# Output_v2_0.net
KiCad netlist of a schematic drawn in EAGLE
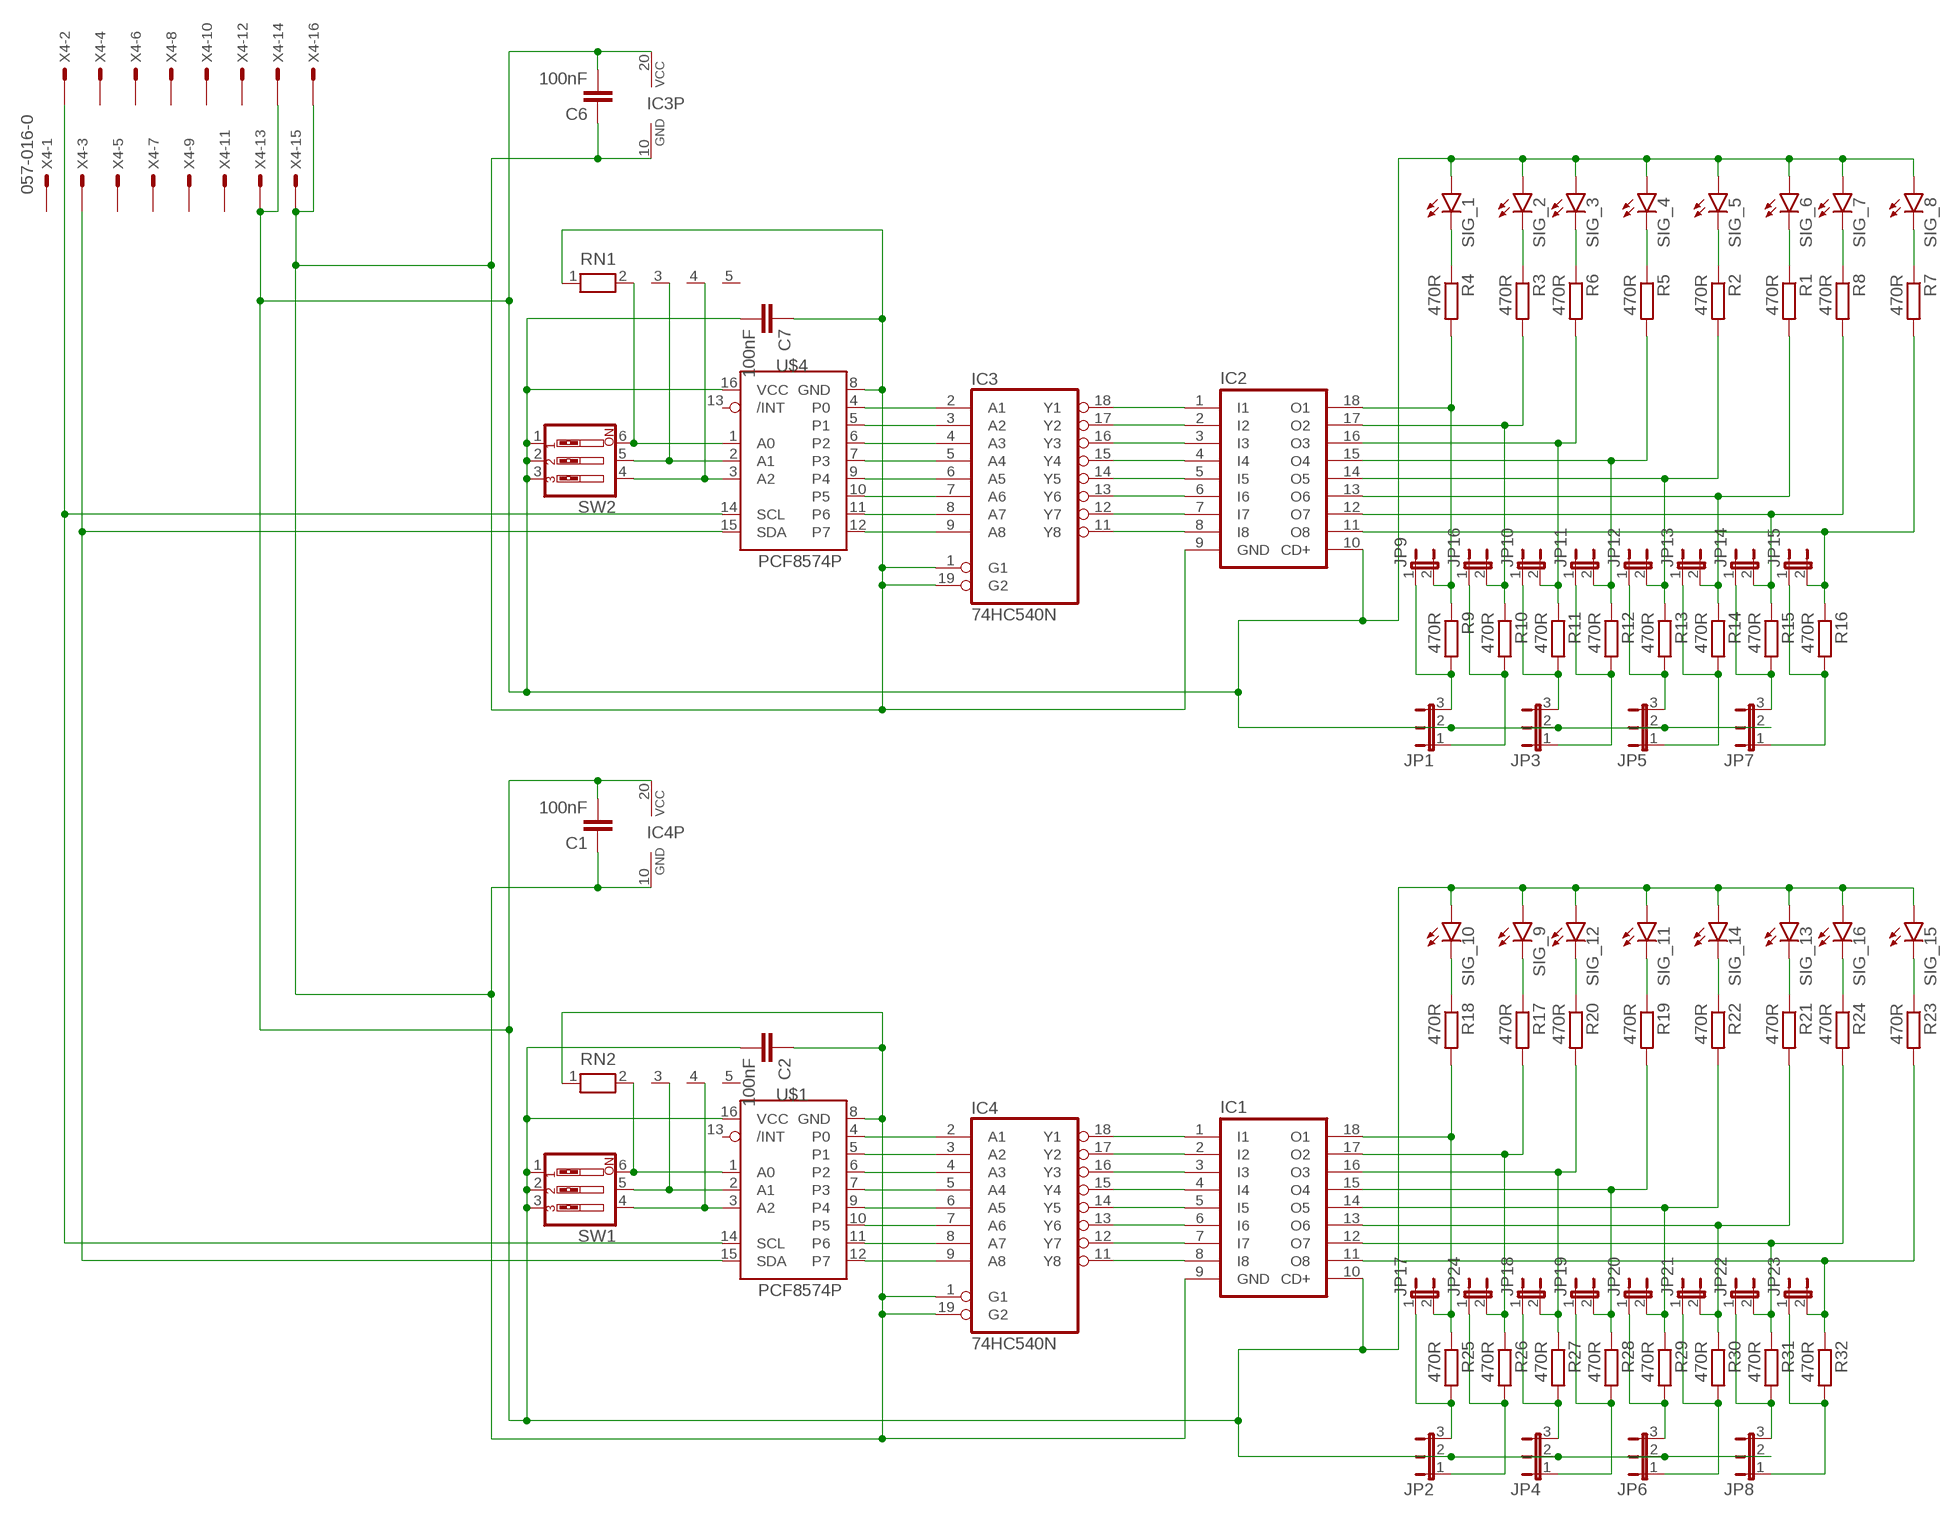
[diagram p0: schematic, sheet 1]

(export (version "E")
  (design (tool "Eeschema 10.0.6"))
  (components
    (comp (ref "C1")
      (value "100nF")
      (footprint "eagle-import:C025-024X044")
      (libsource (lib "eagle-import") (part "C-EU025-024X044"))
    )
    (comp (ref "C2")
      (value "100nF")
      (footprint "eagle-import:C025-024X044")
      (libsource (lib "eagle-import") (part "C-EU025-024X044"))
    )
    (comp (ref "C6")
      (value "100nF")
      (footprint "eagle-import:C025-024X044")
      (libsource (lib "eagle-import") (part "C-EU025-024X044"))
    )
    (comp (ref "C7")
      (value "100nF")
      (footprint "eagle-import:C025-024X044")
      (libsource (lib "eagle-import") (part "C-EU025-024X044"))
    )
    (comp (ref "IC1")
      (value "ULN2803A")
      (footprint "eagle-import:DIL18")
      (libsource (lib "eagle-import") (part "ULN2803A"))
    )
    (comp (ref "IC2")
      (value "ULN2803A")
      (footprint "eagle-import:DIL18")
      (libsource (lib "eagle-import") (part "ULN2803A"))
    )
    (comp (ref "IC3")
      (value "74HC540N")
      (footprint "eagle-import:DIL20")
      (libsource (lib "eagle-import") (part "74540NHC"))
    )
    (comp (ref "IC4")
      (value "74HC540N")
      (footprint "eagle-import:DIL20")
      (libsource (lib "eagle-import") (part "74540NHC"))
    )
    (comp (ref "JP1")
      (value "JP2E")
      (footprint "eagle-import:JP2")
      (libsource (lib "eagle-import") (part "JP2E"))
    )
    (comp (ref "JP2")
      (value "JP2E")
      (footprint "eagle-import:JP2")
      (libsource (lib "eagle-import") (part "JP2E"))
    )
    (comp (ref "JP3")
      (value "JP2E")
      (footprint "eagle-import:JP2")
      (libsource (lib "eagle-import") (part "JP2E"))
    )
    (comp (ref "JP4")
      (value "JP2E")
      (footprint "eagle-import:JP2")
      (libsource (lib "eagle-import") (part "JP2E"))
    )
    (comp (ref "JP5")
      (value "JP2E")
      (footprint "eagle-import:JP2")
      (libsource (lib "eagle-import") (part "JP2E"))
    )
    (comp (ref "JP6")
      (value "JP2E")
      (footprint "eagle-import:JP2")
      (libsource (lib "eagle-import") (part "JP2E"))
    )
    (comp (ref "JP7")
      (value "JP2E")
      (footprint "eagle-import:JP2")
      (libsource (lib "eagle-import") (part "JP2E"))
    )
    (comp (ref "JP8")
      (value "JP2E")
      (footprint "eagle-import:JP2")
      (libsource (lib "eagle-import") (part "JP2E"))
    )
    (comp (ref "JP9")
      (value "JP1E")
      (footprint "eagle-import:JP1")
      (libsource (lib "eagle-import") (part "JP1E"))
    )
    (comp (ref "JP10")
      (value "JP1E")
      (footprint "eagle-import:JP1")
      (libsource (lib "eagle-import") (part "JP1E"))
    )
    (comp (ref "JP11")
      (value "JP1E")
      (footprint "eagle-import:JP1")
      (libsource (lib "eagle-import") (part "JP1E"))
    )
    (comp (ref "JP12")
      (value "JP1E")
      (footprint "eagle-import:JP1")
      (libsource (lib "eagle-import") (part "JP1E"))
    )
    (comp (ref "JP13")
      (value "JP1E")
      (footprint "eagle-import:JP1")
      (libsource (lib "eagle-import") (part "JP1E"))
    )
    (comp (ref "JP14")
      (value "JP1E")
      (footprint "eagle-import:JP1")
      (libsource (lib "eagle-import") (part "JP1E"))
    )
    (comp (ref "JP15")
      (value "JP1E")
      (footprint "eagle-import:JP1")
      (libsource (lib "eagle-import") (part "JP1E"))
    )
    (comp (ref "JP16")
      (value "JP1E")
      (footprint "eagle-import:JP1")
      (libsource (lib "eagle-import") (part "JP1E"))
    )
    (comp (ref "JP17")
      (value "JP1E")
      (footprint "eagle-import:JP1")
      (libsource (lib "eagle-import") (part "JP1E"))
    )
    (comp (ref "JP18")
      (value "JP1E")
      (footprint "eagle-import:JP1")
      (libsource (lib "eagle-import") (part "JP1E"))
    )
    (comp (ref "JP19")
      (value "JP1E")
      (footprint "eagle-import:JP1")
      (libsource (lib "eagle-import") (part "JP1E"))
    )
    (comp (ref "JP20")
      (value "JP1E")
      (footprint "eagle-import:JP1")
      (libsource (lib "eagle-import") (part "JP1E"))
    )
    (comp (ref "JP21")
      (value "JP1E")
      (footprint "eagle-import:JP1")
      (libsource (lib "eagle-import") (part "JP1E"))
    )
    (comp (ref "JP22")
      (value "JP1E")
      (footprint "eagle-import:JP1")
      (libsource (lib "eagle-import") (part "JP1E"))
    )
    (comp (ref "JP23")
      (value "JP1E")
      (footprint "eagle-import:JP1")
      (libsource (lib "eagle-import") (part "JP1E"))
    )
    (comp (ref "JP24")
      (value "JP1E")
      (footprint "eagle-import:JP1")
      (libsource (lib "eagle-import") (part "JP1E"))
    )
    (comp (ref "R1")
      (value "470R")
      (footprint "eagle-import:0309_10")
      (libsource (lib "eagle-import") (part "R-EU_0309/10"))
    )
    (comp (ref "R2")
      (value "470R")
      (footprint "eagle-import:0309_10")
      (libsource (lib "eagle-import") (part "R-EU_0309/10"))
    )
    (comp (ref "R3")
      (value "470R")
      (footprint "eagle-import:0309_10")
      (libsource (lib "eagle-import") (part "R-EU_0309/10"))
    )
    (comp (ref "R4")
      (value "470R")
      (footprint "eagle-import:0309_10")
      (libsource (lib "eagle-import") (part "R-EU_0309/10"))
    )
    (comp (ref "R5")
      (value "470R")
      (footprint "eagle-import:0309_10")
      (libsource (lib "eagle-import") (part "R-EU_0309/10"))
    )
    (comp (ref "R6")
      (value "470R")
      (footprint "eagle-import:0309_10")
      (libsource (lib "eagle-import") (part "R-EU_0309/10"))
    )
    (comp (ref "R7")
      (value "470R")
      (footprint "eagle-import:0309_10")
      (libsource (lib "eagle-import") (part "R-EU_0309/10"))
    )
    (comp (ref "R8")
      (value "470R")
      (footprint "eagle-import:0309_10")
      (libsource (lib "eagle-import") (part "R-EU_0309/10"))
    )
    (comp (ref "R9")
      (value "470R")
      (footprint "eagle-import:0309_10")
      (libsource (lib "eagle-import") (part "R-EU_0309/10"))
    )
    (comp (ref "R10")
      (value "470R")
      (footprint "eagle-import:0309_10")
      (libsource (lib "eagle-import") (part "R-EU_0309/10"))
    )
    (comp (ref "R11")
      (value "470R")
      (footprint "eagle-import:0309_10")
      (libsource (lib "eagle-import") (part "R-EU_0309/10"))
    )
    (comp (ref "R12")
      (value "470R")
      (footprint "eagle-import:0309_10")
      (libsource (lib "eagle-import") (part "R-EU_0309/10"))
    )
    (comp (ref "R13")
      (value "470R")
      (footprint "eagle-import:0309_10")
      (libsource (lib "eagle-import") (part "R-EU_0309/10"))
    )
    (comp (ref "R14")
      (value "470R")
      (footprint "eagle-import:0309_10")
      (libsource (lib "eagle-import") (part "R-EU_0309/10"))
    )
    (comp (ref "R15")
      (value "470R")
      (footprint "eagle-import:0309_10")
      (libsource (lib "eagle-import") (part "R-EU_0309/10"))
    )
    (comp (ref "R16")
      (value "470R")
      (footprint "eagle-import:0309_10")
      (libsource (lib "eagle-import") (part "R-EU_0309/10"))
    )
    (comp (ref "R17")
      (value "470R")
      (footprint "eagle-import:0309_10")
      (libsource (lib "eagle-import") (part "R-EU_0309/10"))
    )
    (comp (ref "R18")
      (value "470R")
      (footprint "eagle-import:0309_10")
      (libsource (lib "eagle-import") (part "R-EU_0309/10"))
    )
    (comp (ref "R19")
      (value "470R")
      (footprint "eagle-import:0309_10")
      (libsource (lib "eagle-import") (part "R-EU_0309/10"))
    )
    (comp (ref "R20")
      (value "470R")
      (footprint "eagle-import:0309_10")
      (libsource (lib "eagle-import") (part "R-EU_0309/10"))
    )
    (comp (ref "R21")
      (value "470R")
      (footprint "eagle-import:0309_10")
      (libsource (lib "eagle-import") (part "R-EU_0309/10"))
    )
    (comp (ref "R22")
      (value "470R")
      (footprint "eagle-import:0309_10")
      (libsource (lib "eagle-import") (part "R-EU_0309/10"))
    )
    (comp (ref "R23")
      (value "470R")
      (footprint "eagle-import:0309_10")
      (libsource (lib "eagle-import") (part "R-EU_0309/10"))
    )
    (comp (ref "R24")
      (value "470R")
      (footprint "eagle-import:0309_10")
      (libsource (lib "eagle-import") (part "R-EU_0309/10"))
    )
    (comp (ref "R25")
      (value "470R")
      (footprint "eagle-import:0309_10")
      (libsource (lib "eagle-import") (part "R-EU_0309/10"))
    )
    (comp (ref "R26")
      (value "470R")
      (footprint "eagle-import:0309_10")
      (libsource (lib "eagle-import") (part "R-EU_0309/10"))
    )
    (comp (ref "R27")
      (value "470R")
      (footprint "eagle-import:0309_10")
      (libsource (lib "eagle-import") (part "R-EU_0309/10"))
    )
    (comp (ref "R28")
      (value "470R")
      (footprint "eagle-import:0309_10")
      (libsource (lib "eagle-import") (part "R-EU_0309/10"))
    )
    (comp (ref "R29")
      (value "470R")
      (footprint "eagle-import:0309_10")
      (libsource (lib "eagle-import") (part "R-EU_0309/10"))
    )
    (comp (ref "R30")
      (value "470R")
      (footprint "eagle-import:0309_10")
      (libsource (lib "eagle-import") (part "R-EU_0309/10"))
    )
    (comp (ref "R31")
      (value "470R")
      (footprint "eagle-import:0309_10")
      (libsource (lib "eagle-import") (part "R-EU_0309/10"))
    )
    (comp (ref "R32")
      (value "470R")
      (footprint "eagle-import:0309_10")
      (libsource (lib "eagle-import") (part "R-EU_0309/10"))
    )
    (comp (ref "RN1")
      (value "RN04")
      (footprint "eagle-import:RN-5")
      (libsource (lib "eagle-import") (part "RN04"))
    )
    (comp (ref "RN2")
      (value "RN04")
      (footprint "eagle-import:RN-5")
      (libsource (lib "eagle-import") (part "RN04"))
    )
    (comp (ref "SIG_1")
      (value "LED3MM")
      (footprint "eagle-import:LED3MM")
      (libsource (lib "eagle-import") (part "LED3MM"))
    )
    (comp (ref "SIG_2")
      (value "LED3MM")
      (footprint "eagle-import:LED3MM")
      (libsource (lib "eagle-import") (part "LED3MM"))
    )
    (comp (ref "SIG_3")
      (value "LED3MM")
      (footprint "eagle-import:LED3MM")
      (libsource (lib "eagle-import") (part "LED3MM"))
    )
    (comp (ref "SIG_4")
      (value "LED3MM")
      (footprint "eagle-import:LED3MM")
      (libsource (lib "eagle-import") (part "LED3MM"))
    )
    (comp (ref "SIG_5")
      (value "LED3MM")
      (footprint "eagle-import:LED3MM")
      (libsource (lib "eagle-import") (part "LED3MM"))
    )
    (comp (ref "SIG_6")
      (value "LED3MM")
      (footprint "eagle-import:LED3MM")
      (libsource (lib "eagle-import") (part "LED3MM"))
    )
    (comp (ref "SIG_7")
      (value "LED3MM")
      (footprint "eagle-import:LED3MM")
      (libsource (lib "eagle-import") (part "LED3MM"))
    )
    (comp (ref "SIG_8")
      (value "LED3MM")
      (footprint "eagle-import:LED3MM")
      (libsource (lib "eagle-import") (part "LED3MM"))
    )
    (comp (ref "SIG_9")
      (value "LED3MM")
      (footprint "eagle-import:LED3MM")
      (libsource (lib "eagle-import") (part "LED3MM"))
    )
    (comp (ref "SIG_10")
      (value "LED3MM")
      (footprint "eagle-import:LED3MM")
      (libsource (lib "eagle-import") (part "LED3MM"))
    )
    (comp (ref "SIG_11")
      (value "LED3MM")
      (footprint "eagle-import:LED3MM")
      (libsource (lib "eagle-import") (part "LED3MM"))
    )
    (comp (ref "SIG_12")
      (value "LED3MM")
      (footprint "eagle-import:LED3MM")
      (libsource (lib "eagle-import") (part "LED3MM"))
    )
    (comp (ref "SIG_13")
      (value "LED3MM")
      (footprint "eagle-import:LED3MM")
      (libsource (lib "eagle-import") (part "LED3MM"))
    )
    (comp (ref "SIG_14")
      (value "LED3MM")
      (footprint "eagle-import:LED3MM")
      (libsource (lib "eagle-import") (part "LED3MM"))
    )
    (comp (ref "SIG_15")
      (value "LED3MM")
      (footprint "eagle-import:LED3MM")
      (libsource (lib "eagle-import") (part "LED3MM"))
    )
    (comp (ref "SIG_16")
      (value "LED3MM")
      (footprint "eagle-import:LED3MM")
      (libsource (lib "eagle-import") (part "LED3MM"))
    )
    (comp (ref "SW1")
      (value "SW_DIP-3")
      (footprint "eagle-import:EDG-03")
      (libsource (lib "eagle-import") (part "SW_DIP-3"))
    )
    (comp (ref "SW2")
      (value "SW_DIP-3")
      (footprint "eagle-import:EDG-03")
      (libsource (lib "eagle-import") (part "SW_DIP-3"))
    )
    (comp (ref "U$1")
      (value "PCF8574P")
      (footprint "eagle-import:DIL16")
      (libsource (lib "eagle-import") (part "PCF8574P"))
    )
    (comp (ref "U$4")
      (value "PCF8574P")
      (footprint "eagle-import:DIL16")
      (libsource (lib "eagle-import") (part "PCF8574P"))
    )
    (comp (ref "X4")
      (value "057-016-0")
      (footprint "eagle-import:057-016-0")
      (libsource (lib "eagle-import") (part "057-016-0"))
    )
  )
  (nets
    (net (code "1") (name "Net-(IC1-CD+)") (class "Default")
      (node (ref "C1") (pin "2") (pinfunction "2_2") (pintype "passive"))
      (node (ref "C2") (pin "2") (pinfunction "2_2") (pintype "passive"))
      (node (ref "C6") (pin "2") (pinfunction "2_2") (pintype "passive"))
      (node (ref "C7") (pin "2") (pinfunction "2_2") (pintype "passive"))
      (node (ref "IC1") (pin "10") (pinfunction "CD+_10") (pintype "passive"))
      (node (ref "IC2") (pin "10") (pinfunction "CD+_10") (pintype "passive"))
      (node (ref "IC3") (pin "20") (pinfunction "VCC_20") (pintype "power_in"))
      (node (ref "IC4") (pin "20") (pinfunction "VCC_20") (pintype "power_in"))
      (node (ref "JP1") (pin "2") (pinfunction "2_2") (pintype "passive"))
      (node (ref "JP2") (pin "2") (pinfunction "2_2") (pintype "passive"))
      (node (ref "JP3") (pin "2") (pinfunction "2_2") (pintype "passive"))
      (node (ref "JP4") (pin "2") (pinfunction "2_2") (pintype "passive"))
      (node (ref "JP5") (pin "2") (pinfunction "2_2") (pintype "passive"))
      (node (ref "JP6") (pin "2") (pinfunction "2_2") (pintype "passive"))
      (node (ref "JP7") (pin "2") (pinfunction "2_2") (pintype "passive"))
      (node (ref "JP8") (pin "2") (pinfunction "2_2") (pintype "passive"))
      (node (ref "SIG_1") (pin "A") (pinfunction "A_A") (pintype "passive"))
      (node (ref "SIG_10") (pin "A") (pinfunction "A_A") (pintype "passive"))
      (node (ref "SIG_11") (pin "A") (pinfunction "A_A") (pintype "passive"))
      (node (ref "SIG_12") (pin "A") (pinfunction "A_A") (pintype "passive"))
      (node (ref "SIG_13") (pin "A") (pinfunction "A_A") (pintype "passive"))
      (node (ref "SIG_14") (pin "A") (pinfunction "A_A") (pintype "passive"))
      (node (ref "SIG_15") (pin "A") (pinfunction "A_A") (pintype "passive"))
      (node (ref "SIG_16") (pin "A") (pinfunction "A_A") (pintype "passive"))
      (node (ref "SIG_2") (pin "A") (pinfunction "A_A") (pintype "passive"))
      (node (ref "SIG_3") (pin "A") (pinfunction "A_A") (pintype "passive"))
      (node (ref "SIG_4") (pin "A") (pinfunction "A_A") (pintype "passive"))
      (node (ref "SIG_5") (pin "A") (pinfunction "A_A") (pintype "passive"))
      (node (ref "SIG_6") (pin "A") (pinfunction "A_A") (pintype "passive"))
      (node (ref "SIG_7") (pin "A") (pinfunction "A_A") (pintype "passive"))
      (node (ref "SIG_8") (pin "A") (pinfunction "A_A") (pintype "passive"))
      (node (ref "SIG_9") (pin "A") (pinfunction "A_A") (pintype "passive"))
      (node (ref "SW1") (pin "1") (pinfunction "1_1") (pintype "passive"))
      (node (ref "SW1") (pin "2") (pinfunction "2_2") (pintype "passive"))
      (node (ref "SW1") (pin "3") (pinfunction "3_3") (pintype "passive"))
      (node (ref "SW2") (pin "1") (pinfunction "1_1") (pintype "passive"))
      (node (ref "SW2") (pin "2") (pinfunction "2_2") (pintype "passive"))
      (node (ref "SW2") (pin "3") (pinfunction "3_3") (pintype "passive"))
      (node (ref "U$1") (pin "16") (pinfunction "VCC_16") (pintype "power_in"))
      (node (ref "U$4") (pin "16") (pinfunction "VCC_16") (pintype "power_in"))
      (node (ref "X4") (pin "13") (pinfunction "S_13") (pintype "passive"))
      (node (ref "X4") (pin "14") (pinfunction "S_14") (pintype "passive"))
    )
    (net (code "2") (name "Net-(IC1-GND)") (class "Default")
      (node (ref "C1") (pin "1") (pinfunction "1_1") (pintype "passive"))
      (node (ref "C2") (pin "1") (pinfunction "1_1") (pintype "passive"))
      (node (ref "C6") (pin "1") (pinfunction "1_1") (pintype "passive"))
      (node (ref "C7") (pin "1") (pinfunction "1_1") (pintype "passive"))
      (node (ref "IC1") (pin "9") (pinfunction "GND_9") (pintype "power_in"))
      (node (ref "IC2") (pin "9") (pinfunction "GND_9") (pintype "power_in"))
      (node (ref "IC3") (pin "1") (pinfunction "G1_1") (pintype "input"))
      (node (ref "IC3") (pin "10") (pinfunction "GND_10") (pintype "power_in"))
      (node (ref "IC3") (pin "19") (pinfunction "G2_19") (pintype "input"))
      (node (ref "IC4") (pin "1") (pinfunction "G1_1") (pintype "input"))
      (node (ref "IC4") (pin "10") (pinfunction "GND_10") (pintype "power_in"))
      (node (ref "IC4") (pin "19") (pinfunction "G2_19") (pintype "input"))
      (node (ref "RN1") (pin "1") (pinfunction "1_1") (pintype "passive"))
      (node (ref "RN2") (pin "1") (pinfunction "1_1") (pintype "passive"))
      (node (ref "U$1") (pin "8") (pinfunction "GND_8") (pintype "power_in"))
      (node (ref "U$4") (pin "8") (pinfunction "GND_8") (pintype "power_in"))
      (node (ref "X4") (pin "15") (pinfunction "S_15") (pintype "passive"))
      (node (ref "X4") (pin "16") (pinfunction "S_16") (pintype "passive"))
    )
    (net (code "3") (name "Net-(IC1-I1)") (class "Default")
      (node (ref "IC1") (pin "1") (pinfunction "I1_1") (pintype "input"))
      (node (ref "IC4") (pin "18") (pinfunction "Y1_18") (pintype "tri_state"))
    )
    (net (code "4") (name "Net-(IC1-I2)") (class "Default")
      (node (ref "IC1") (pin "2") (pinfunction "I2_2") (pintype "input"))
      (node (ref "IC4") (pin "17") (pinfunction "Y2_17") (pintype "tri_state"))
    )
    (net (code "5") (name "Net-(IC1-I3)") (class "Default")
      (node (ref "IC1") (pin "3") (pinfunction "I3_3") (pintype "input"))
      (node (ref "IC4") (pin "16") (pinfunction "Y3_16") (pintype "tri_state"))
    )
    (net (code "6") (name "Net-(IC1-I4)") (class "Default")
      (node (ref "IC1") (pin "4") (pinfunction "I4_4") (pintype "input"))
      (node (ref "IC4") (pin "15") (pinfunction "Y4_15") (pintype "tri_state"))
    )
    (net (code "7") (name "Net-(IC1-I5)") (class "Default")
      (node (ref "IC1") (pin "5") (pinfunction "I5_5") (pintype "input"))
      (node (ref "IC4") (pin "14") (pinfunction "Y5_14") (pintype "tri_state"))
    )
    (net (code "8") (name "Net-(IC1-I6)") (class "Default")
      (node (ref "IC1") (pin "6") (pinfunction "I6_6") (pintype "input"))
      (node (ref "IC4") (pin "13") (pinfunction "Y6_13") (pintype "tri_state"))
    )
    (net (code "9") (name "Net-(IC1-I7)") (class "Default")
      (node (ref "IC1") (pin "7") (pinfunction "I7_7") (pintype "input"))
      (node (ref "IC4") (pin "12") (pinfunction "Y7_12") (pintype "tri_state"))
    )
    (net (code "10") (name "Net-(IC1-I8)") (class "Default")
      (node (ref "IC1") (pin "8") (pinfunction "I8_8") (pintype "input"))
      (node (ref "IC4") (pin "11") (pinfunction "Y8_11") (pintype "tri_state"))
    )
    (net (code "11") (name "Net-(IC1-O1)") (class "Default")
      (node (ref "IC1") (pin "18") (pinfunction "O1_18") (pintype "open_collector"))
      (node (ref "JP17") (pin "2") (pinfunction "2_2") (pintype "passive"))
      (node (ref "R18") (pin "2") (pinfunction "2_2") (pintype "passive"))
      (node (ref "R25") (pin "1") (pinfunction "1_1") (pintype "passive"))
    )
    (net (code "12") (name "Net-(IC1-O2)") (class "Default")
      (node (ref "IC1") (pin "17") (pinfunction "O2_17") (pintype "open_collector"))
      (node (ref "JP24") (pin "2") (pinfunction "2_2") (pintype "passive"))
      (node (ref "R17") (pin "2") (pinfunction "2_2") (pintype "passive"))
      (node (ref "R26") (pin "1") (pinfunction "1_1") (pintype "passive"))
    )
    (net (code "13") (name "Net-(IC1-O3)") (class "Default")
      (node (ref "IC1") (pin "16") (pinfunction "O3_16") (pintype "open_collector"))
      (node (ref "JP18") (pin "2") (pinfunction "2_2") (pintype "passive"))
      (node (ref "R20") (pin "2") (pinfunction "2_2") (pintype "passive"))
      (node (ref "R27") (pin "1") (pinfunction "1_1") (pintype "passive"))
    )
    (net (code "14") (name "Net-(IC1-O4)") (class "Default")
      (node (ref "IC1") (pin "15") (pinfunction "O4_15") (pintype "open_collector"))
      (node (ref "JP19") (pin "2") (pinfunction "2_2") (pintype "passive"))
      (node (ref "R19") (pin "2") (pinfunction "2_2") (pintype "passive"))
      (node (ref "R28") (pin "1") (pinfunction "1_1") (pintype "passive"))
    )
    (net (code "15") (name "Net-(IC1-O5)") (class "Default")
      (node (ref "IC1") (pin "14") (pinfunction "O5_14") (pintype "open_collector"))
      (node (ref "JP20") (pin "2") (pinfunction "2_2") (pintype "passive"))
      (node (ref "R22") (pin "2") (pinfunction "2_2") (pintype "passive"))
      (node (ref "R29") (pin "1") (pinfunction "1_1") (pintype "passive"))
    )
    (net (code "16") (name "Net-(IC1-O6)") (class "Default")
      (node (ref "IC1") (pin "13") (pinfunction "O6_13") (pintype "open_collector"))
      (node (ref "JP21") (pin "2") (pinfunction "2_2") (pintype "passive"))
      (node (ref "R21") (pin "2") (pinfunction "2_2") (pintype "passive"))
      (node (ref "R30") (pin "1") (pinfunction "1_1") (pintype "passive"))
    )
    (net (code "17") (name "Net-(IC1-O7)") (class "Default")
      (node (ref "IC1") (pin "12") (pinfunction "O7_12") (pintype "open_collector"))
      (node (ref "JP22") (pin "2") (pinfunction "2_2") (pintype "passive"))
      (node (ref "R24") (pin "2") (pinfunction "2_2") (pintype "passive"))
      (node (ref "R31") (pin "1") (pinfunction "1_1") (pintype "passive"))
    )
    (net (code "18") (name "Net-(IC1-O8)") (class "Default")
      (node (ref "IC1") (pin "11") (pinfunction "O8_11") (pintype "open_collector"))
      (node (ref "JP23") (pin "2") (pinfunction "2_2") (pintype "passive"))
      (node (ref "R23") (pin "2") (pinfunction "2_2") (pintype "passive"))
      (node (ref "R32") (pin "1") (pinfunction "1_1") (pintype "passive"))
    )
    (net (code "19") (name "Net-(IC2-I1)") (class "Default")
      (node (ref "IC2") (pin "1") (pinfunction "I1_1") (pintype "input"))
      (node (ref "IC3") (pin "18") (pinfunction "Y1_18") (pintype "tri_state"))
    )
    (net (code "20") (name "Net-(IC2-I2)") (class "Default")
      (node (ref "IC2") (pin "2") (pinfunction "I2_2") (pintype "input"))
      (node (ref "IC3") (pin "17") (pinfunction "Y2_17") (pintype "tri_state"))
    )
    (net (code "21") (name "Net-(IC2-I3)") (class "Default")
      (node (ref "IC2") (pin "3") (pinfunction "I3_3") (pintype "input"))
      (node (ref "IC3") (pin "16") (pinfunction "Y3_16") (pintype "tri_state"))
    )
    (net (code "22") (name "Net-(IC2-I4)") (class "Default")
      (node (ref "IC2") (pin "4") (pinfunction "I4_4") (pintype "input"))
      (node (ref "IC3") (pin "15") (pinfunction "Y4_15") (pintype "tri_state"))
    )
    (net (code "23") (name "Net-(IC2-I5)") (class "Default")
      (node (ref "IC2") (pin "5") (pinfunction "I5_5") (pintype "input"))
      (node (ref "IC3") (pin "14") (pinfunction "Y5_14") (pintype "tri_state"))
    )
    (net (code "24") (name "Net-(IC2-I6)") (class "Default")
      (node (ref "IC2") (pin "6") (pinfunction "I6_6") (pintype "input"))
      (node (ref "IC3") (pin "13") (pinfunction "Y6_13") (pintype "tri_state"))
    )
    (net (code "25") (name "Net-(IC2-I7)") (class "Default")
      (node (ref "IC2") (pin "7") (pinfunction "I7_7") (pintype "input"))
      (node (ref "IC3") (pin "12") (pinfunction "Y7_12") (pintype "tri_state"))
    )
    (net (code "26") (name "Net-(IC2-I8)") (class "Default")
      (node (ref "IC2") (pin "8") (pinfunction "I8_8") (pintype "input"))
      (node (ref "IC3") (pin "11") (pinfunction "Y8_11") (pintype "tri_state"))
    )
    (net (code "27") (name "Net-(IC2-O1)") (class "Default")
      (node (ref "IC2") (pin "18") (pinfunction "O1_18") (pintype "open_collector"))
      (node (ref "JP9") (pin "2") (pinfunction "2_2") (pintype "passive"))
      (node (ref "R4") (pin "2") (pinfunction "2_2") (pintype "passive"))
      (node (ref "R9") (pin "1") (pinfunction "1_1") (pintype "passive"))
    )
    (net (code "28") (name "Net-(IC2-O2)") (class "Default")
      (node (ref "IC2") (pin "17") (pinfunction "O2_17") (pintype "open_collector"))
      (node (ref "JP16") (pin "2") (pinfunction "2_2") (pintype "passive"))
      (node (ref "R10") (pin "1") (pinfunction "1_1") (pintype "passive"))
      (node (ref "R3") (pin "2") (pinfunction "2_2") (pintype "passive"))
    )
    (net (code "29") (name "Net-(IC2-O3)") (class "Default")
      (node (ref "IC2") (pin "16") (pinfunction "O3_16") (pintype "open_collector"))
      (node (ref "JP10") (pin "2") (pinfunction "2_2") (pintype "passive"))
      (node (ref "R11") (pin "1") (pinfunction "1_1") (pintype "passive"))
      (node (ref "R6") (pin "2") (pinfunction "2_2") (pintype "passive"))
    )
    (net (code "30") (name "Net-(IC2-O4)") (class "Default")
      (node (ref "IC2") (pin "15") (pinfunction "O4_15") (pintype "open_collector"))
      (node (ref "JP11") (pin "2") (pinfunction "2_2") (pintype "passive"))
      (node (ref "R12") (pin "1") (pinfunction "1_1") (pintype "passive"))
      (node (ref "R5") (pin "2") (pinfunction "2_2") (pintype "passive"))
    )
    (net (code "31") (name "Net-(IC2-O5)") (class "Default")
      (node (ref "IC2") (pin "14") (pinfunction "O5_14") (pintype "open_collector"))
      (node (ref "JP12") (pin "2") (pinfunction "2_2") (pintype "passive"))
      (node (ref "R13") (pin "1") (pinfunction "1_1") (pintype "passive"))
      (node (ref "R2") (pin "2") (pinfunction "2_2") (pintype "passive"))
    )
    (net (code "32") (name "Net-(IC2-O6)") (class "Default")
      (node (ref "IC2") (pin "13") (pinfunction "O6_13") (pintype "open_collector"))
      (node (ref "JP13") (pin "2") (pinfunction "2_2") (pintype "passive"))
      (node (ref "R1") (pin "2") (pinfunction "2_2") (pintype "passive"))
      (node (ref "R14") (pin "1") (pinfunction "1_1") (pintype "passive"))
    )
    (net (code "33") (name "Net-(IC2-O7)") (class "Default")
      (node (ref "IC2") (pin "12") (pinfunction "O7_12") (pintype "open_collector"))
      (node (ref "JP14") (pin "2") (pinfunction "2_2") (pintype "passive"))
      (node (ref "R15") (pin "1") (pinfunction "1_1") (pintype "passive"))
      (node (ref "R8") (pin "2") (pinfunction "2_2") (pintype "passive"))
    )
    (net (code "34") (name "Net-(IC2-O8)") (class "Default")
      (node (ref "IC2") (pin "11") (pinfunction "O8_11") (pintype "open_collector"))
      (node (ref "JP15") (pin "2") (pinfunction "2_2") (pintype "passive"))
      (node (ref "R16") (pin "1") (pinfunction "1_1") (pintype "passive"))
      (node (ref "R7") (pin "2") (pinfunction "2_2") (pintype "passive"))
    )
    (net (code "35") (name "Net-(IC3A-A1)") (class "Default")
      (node (ref "IC3") (pin "2") (pinfunction "A1_2") (pintype "input"))
      (node (ref "U$4") (pin "4") (pinfunction "P0_4") (pintype "bidirectional"))
    )
    (net (code "36") (name "Net-(IC3A-A2)") (class "Default")
      (node (ref "IC3") (pin "3") (pinfunction "A2_3") (pintype "input"))
      (node (ref "U$4") (pin "5") (pinfunction "P1_5") (pintype "bidirectional"))
    )
    (net (code "37") (name "Net-(IC3A-A3)") (class "Default")
      (node (ref "IC3") (pin "4") (pinfunction "A3_4") (pintype "input"))
      (node (ref "U$4") (pin "6") (pinfunction "P2_6") (pintype "bidirectional"))
    )
    (net (code "38") (name "Net-(IC3A-A4)") (class "Default")
      (node (ref "IC3") (pin "5") (pinfunction "A4_5") (pintype "input"))
      (node (ref "U$4") (pin "7") (pinfunction "P3_7") (pintype "bidirectional"))
    )
    (net (code "39") (name "Net-(IC3A-A5)") (class "Default")
      (node (ref "IC3") (pin "6") (pinfunction "A5_6") (pintype "input"))
      (node (ref "U$4") (pin "9") (pinfunction "P4_9") (pintype "bidirectional"))
    )
    (net (code "40") (name "Net-(IC3A-A6)") (class "Default")
      (node (ref "IC3") (pin "7") (pinfunction "A6_7") (pintype "input"))
      (node (ref "U$4") (pin "10") (pinfunction "P5_10") (pintype "bidirectional"))
    )
    (net (code "41") (name "Net-(IC3A-A7)") (class "Default")
      (node (ref "IC3") (pin "8") (pinfunction "A7_8") (pintype "input"))
      (node (ref "U$4") (pin "11") (pinfunction "P6_11") (pintype "bidirectional"))
    )
    (net (code "42") (name "Net-(IC3A-A8)") (class "Default")
      (node (ref "IC3") (pin "9") (pinfunction "A8_9") (pintype "input"))
      (node (ref "U$4") (pin "12") (pinfunction "P7_12") (pintype "bidirectional"))
    )
    (net (code "43") (name "Net-(IC4A-A1)") (class "Default")
      (node (ref "IC4") (pin "2") (pinfunction "A1_2") (pintype "input"))
      (node (ref "U$1") (pin "4") (pinfunction "P0_4") (pintype "bidirectional"))
    )
    (net (code "44") (name "Net-(IC4A-A2)") (class "Default")
      (node (ref "IC4") (pin "3") (pinfunction "A2_3") (pintype "input"))
      (node (ref "U$1") (pin "5") (pinfunction "P1_5") (pintype "bidirectional"))
    )
    (net (code "45") (name "Net-(IC4A-A3)") (class "Default")
      (node (ref "IC4") (pin "4") (pinfunction "A3_4") (pintype "input"))
      (node (ref "U$1") (pin "6") (pinfunction "P2_6") (pintype "bidirectional"))
    )
    (net (code "46") (name "Net-(IC4A-A4)") (class "Default")
      (node (ref "IC4") (pin "5") (pinfunction "A4_5") (pintype "input"))
      (node (ref "U$1") (pin "7") (pinfunction "P3_7") (pintype "bidirectional"))
    )
    (net (code "47") (name "Net-(IC4A-A5)") (class "Default")
      (node (ref "IC4") (pin "6") (pinfunction "A5_6") (pintype "input"))
      (node (ref "U$1") (pin "9") (pinfunction "P4_9") (pintype "bidirectional"))
    )
    (net (code "48") (name "Net-(IC4A-A6)") (class "Default")
      (node (ref "IC4") (pin "7") (pinfunction "A6_7") (pintype "input"))
      (node (ref "U$1") (pin "10") (pinfunction "P5_10") (pintype "bidirectional"))
    )
    (net (code "49") (name "Net-(IC4A-A7)") (class "Default")
      (node (ref "IC4") (pin "8") (pinfunction "A7_8") (pintype "input"))
      (node (ref "U$1") (pin "11") (pinfunction "P6_11") (pintype "bidirectional"))
    )
    (net (code "50") (name "Net-(IC4A-A8)") (class "Default")
      (node (ref "IC4") (pin "9") (pinfunction "A8_9") (pintype "input"))
      (node (ref "U$1") (pin "12") (pinfunction "P7_12") (pintype "bidirectional"))
    )
    (net (code "51") (name "Net-(JP1-Pad1)") (class "Default")
      (node (ref "JP1") (pin "1") (pinfunction "1_1") (pintype "passive"))
      (node (ref "JP16") (pin "1") (pinfunction "1_1") (pintype "passive"))
      (node (ref "R10") (pin "2") (pinfunction "2_2") (pintype "passive"))
    )
    (net (code "52") (name "Net-(JP1-Pad3)") (class "Default")
      (node (ref "JP1") (pin "3") (pinfunction "3_3") (pintype "passive"))
      (node (ref "JP9") (pin "1") (pinfunction "1_1") (pintype "passive"))
      (node (ref "R9") (pin "2") (pinfunction "2_2") (pintype "passive"))
    )
    (net (code "53") (name "Net-(JP2-Pad1)") (class "Default")
      (node (ref "JP2") (pin "1") (pinfunction "1_1") (pintype "passive"))
      (node (ref "JP24") (pin "1") (pinfunction "1_1") (pintype "passive"))
      (node (ref "R26") (pin "2") (pinfunction "2_2") (pintype "passive"))
    )
    (net (code "54") (name "Net-(JP10-Pad1)") (class "Default")
      (node (ref "JP10") (pin "1") (pinfunction "1_1") (pintype "passive"))
      (node (ref "JP3") (pin "3") (pinfunction "3_3") (pintype "passive"))
      (node (ref "R11") (pin "2") (pinfunction "2_2") (pintype "passive"))
    )
    (net (code "55") (name "Net-(JP11-Pad1)") (class "Default")
      (node (ref "JP11") (pin "1") (pinfunction "1_1") (pintype "passive"))
      (node (ref "JP3") (pin "1") (pinfunction "1_1") (pintype "passive"))
      (node (ref "R12") (pin "2") (pinfunction "2_2") (pintype "passive"))
    )
    (net (code "56") (name "Net-(JP12-Pad1)") (class "Default")
      (node (ref "JP12") (pin "1") (pinfunction "1_1") (pintype "passive"))
      (node (ref "JP5") (pin "3") (pinfunction "3_3") (pintype "passive"))
      (node (ref "R13") (pin "2") (pinfunction "2_2") (pintype "passive"))
    )
    (net (code "57") (name "Net-(JP13-Pad1)") (class "Default")
      (node (ref "JP13") (pin "1") (pinfunction "1_1") (pintype "passive"))
      (node (ref "JP5") (pin "1") (pinfunction "1_1") (pintype "passive"))
      (node (ref "R14") (pin "2") (pinfunction "2_2") (pintype "passive"))
    )
    (net (code "58") (name "Net-(JP14-Pad1)") (class "Default")
      (node (ref "JP14") (pin "1") (pinfunction "1_1") (pintype "passive"))
      (node (ref "JP7") (pin "3") (pinfunction "3_3") (pintype "passive"))
      (node (ref "R15") (pin "2") (pinfunction "2_2") (pintype "passive"))
    )
    (net (code "59") (name "Net-(JP15-Pad1)") (class "Default")
      (node (ref "JP15") (pin "1") (pinfunction "1_1") (pintype "passive"))
      (node (ref "JP7") (pin "1") (pinfunction "1_1") (pintype "passive"))
      (node (ref "R16") (pin "2") (pinfunction "2_2") (pintype "passive"))
    )
    (net (code "60") (name "Net-(JP17-Pad1)") (class "Default")
      (node (ref "JP17") (pin "1") (pinfunction "1_1") (pintype "passive"))
      (node (ref "JP2") (pin "3") (pinfunction "3_3") (pintype "passive"))
      (node (ref "R25") (pin "2") (pinfunction "2_2") (pintype "passive"))
    )
    (net (code "61") (name "Net-(JP18-Pad1)") (class "Default")
      (node (ref "JP18") (pin "1") (pinfunction "1_1") (pintype "passive"))
      (node (ref "JP4") (pin "3") (pinfunction "3_3") (pintype "passive"))
      (node (ref "R27") (pin "2") (pinfunction "2_2") (pintype "passive"))
    )
    (net (code "62") (name "Net-(JP19-Pad1)") (class "Default")
      (node (ref "JP19") (pin "1") (pinfunction "1_1") (pintype "passive"))
      (node (ref "JP4") (pin "1") (pinfunction "1_1") (pintype "passive"))
      (node (ref "R28") (pin "2") (pinfunction "2_2") (pintype "passive"))
    )
    (net (code "63") (name "Net-(JP20-Pad1)") (class "Default")
      (node (ref "JP20") (pin "1") (pinfunction "1_1") (pintype "passive"))
      (node (ref "JP6") (pin "3") (pinfunction "3_3") (pintype "passive"))
      (node (ref "R29") (pin "2") (pinfunction "2_2") (pintype "passive"))
    )
    (net (code "64") (name "Net-(JP21-Pad1)") (class "Default")
      (node (ref "JP21") (pin "1") (pinfunction "1_1") (pintype "passive"))
      (node (ref "JP6") (pin "1") (pinfunction "1_1") (pintype "passive"))
      (node (ref "R30") (pin "2") (pinfunction "2_2") (pintype "passive"))
    )
    (net (code "65") (name "Net-(JP22-Pad1)") (class "Default")
      (node (ref "JP22") (pin "1") (pinfunction "1_1") (pintype "passive"))
      (node (ref "JP8") (pin "3") (pinfunction "3_3") (pintype "passive"))
      (node (ref "R31") (pin "2") (pinfunction "2_2") (pintype "passive"))
    )
    (net (code "66") (name "Net-(JP23-Pad1)") (class "Default")
      (node (ref "JP23") (pin "1") (pinfunction "1_1") (pintype "passive"))
      (node (ref "JP8") (pin "1") (pinfunction "1_1") (pintype "passive"))
      (node (ref "R32") (pin "2") (pinfunction "2_2") (pintype "passive"))
    )
    (net (code "67") (name "Net-(SIG_1-C)") (class "Default")
      (node (ref "R4") (pin "1") (pinfunction "1_1") (pintype "passive"))
      (node (ref "SIG_1") (pin "K") (pinfunction "C_K") (pintype "passive"))
    )
    (net (code "68") (name "Net-(SIG_2-C)") (class "Default")
      (node (ref "R3") (pin "1") (pinfunction "1_1") (pintype "passive"))
      (node (ref "SIG_2") (pin "K") (pinfunction "C_K") (pintype "passive"))
    )
    (net (code "69") (name "Net-(SIG_3-C)") (class "Default")
      (node (ref "R6") (pin "1") (pinfunction "1_1") (pintype "passive"))
      (node (ref "SIG_3") (pin "K") (pinfunction "C_K") (pintype "passive"))
    )
    (net (code "70") (name "Net-(SIG_4-C)") (class "Default")
      (node (ref "R5") (pin "1") (pinfunction "1_1") (pintype "passive"))
      (node (ref "SIG_4") (pin "K") (pinfunction "C_K") (pintype "passive"))
    )
    (net (code "71") (name "Net-(SIG_5-C)") (class "Default")
      (node (ref "R2") (pin "1") (pinfunction "1_1") (pintype "passive"))
      (node (ref "SIG_5") (pin "K") (pinfunction "C_K") (pintype "passive"))
    )
    (net (code "72") (name "Net-(SIG_6-C)") (class "Default")
      (node (ref "R1") (pin "1") (pinfunction "1_1") (pintype "passive"))
      (node (ref "SIG_6") (pin "K") (pinfunction "C_K") (pintype "passive"))
    )
    (net (code "73") (name "Net-(SIG_7-C)") (class "Default")
      (node (ref "R8") (pin "1") (pinfunction "1_1") (pintype "passive"))
      (node (ref "SIG_7") (pin "K") (pinfunction "C_K") (pintype "passive"))
    )
    (net (code "74") (name "Net-(SIG_8-C)") (class "Default")
      (node (ref "R7") (pin "1") (pinfunction "1_1") (pintype "passive"))
      (node (ref "SIG_8") (pin "K") (pinfunction "C_K") (pintype "passive"))
    )
    (net (code "75") (name "Net-(SIG_9-C)") (class "Default")
      (node (ref "R17") (pin "1") (pinfunction "1_1") (pintype "passive"))
      (node (ref "SIG_9") (pin "K") (pinfunction "C_K") (pintype "passive"))
    )
    (net (code "76") (name "Net-(SIG_10-C)") (class "Default")
      (node (ref "R18") (pin "1") (pinfunction "1_1") (pintype "passive"))
      (node (ref "SIG_10") (pin "K") (pinfunction "C_K") (pintype "passive"))
    )
    (net (code "77") (name "Net-(SIG_11-C)") (class "Default")
      (node (ref "R19") (pin "1") (pinfunction "1_1") (pintype "passive"))
      (node (ref "SIG_11") (pin "K") (pinfunction "C_K") (pintype "passive"))
    )
    (net (code "78") (name "Net-(SIG_12-C)") (class "Default")
      (node (ref "R20") (pin "1") (pinfunction "1_1") (pintype "passive"))
      (node (ref "SIG_12") (pin "K") (pinfunction "C_K") (pintype "passive"))
    )
    (net (code "79") (name "Net-(SIG_13-C)") (class "Default")
      (node (ref "R21") (pin "1") (pinfunction "1_1") (pintype "passive"))
      (node (ref "SIG_13") (pin "K") (pinfunction "C_K") (pintype "passive"))
    )
    (net (code "80") (name "Net-(SIG_14-C)") (class "Default")
      (node (ref "R22") (pin "1") (pinfunction "1_1") (pintype "passive"))
      (node (ref "SIG_14") (pin "K") (pinfunction "C_K") (pintype "passive"))
    )
    (net (code "81") (name "Net-(SIG_15-C)") (class "Default")
      (node (ref "R23") (pin "1") (pinfunction "1_1") (pintype "passive"))
      (node (ref "SIG_15") (pin "K") (pinfunction "C_K") (pintype "passive"))
    )
    (net (code "82") (name "Net-(SIG_16-C)") (class "Default")
      (node (ref "R24") (pin "1") (pinfunction "1_1") (pintype "passive"))
      (node (ref "SIG_16") (pin "K") (pinfunction "C_K") (pintype "passive"))
    )
    (net (code "83") (name "Net-(U$1-A0)") (class "Default")
      (node (ref "RN2") (pin "2") (pinfunction "2_2") (pintype "passive"))
      (node (ref "SW1") (pin "6") (pinfunction "6_6") (pintype "passive"))
      (node (ref "U$1") (pin "1") (pinfunction "A0_1") (pintype "input"))
    )
    (net (code "84") (name "Net-(U$1-A1)") (class "Default")
      (node (ref "RN2") (pin "3") (pinfunction "3_3") (pintype "passive"))
      (node (ref "SW1") (pin "5") (pinfunction "5_5") (pintype "passive"))
      (node (ref "U$1") (pin "2") (pinfunction "A1_2") (pintype "input"))
    )
    (net (code "85") (name "Net-(U$1-A2)") (class "Default")
      (node (ref "RN2") (pin "4") (pinfunction "4_4") (pintype "passive"))
      (node (ref "SW1") (pin "4") (pinfunction "4_4") (pintype "passive"))
      (node (ref "U$1") (pin "3") (pinfunction "A2_3") (pintype "input"))
    )
    (net (code "86") (name "Net-(U$1-SCL)") (class "Default")
      (node (ref "U$1") (pin "14") (pinfunction "SCL_14") (pintype "input"))
      (node (ref "U$4") (pin "14") (pinfunction "SCL_14") (pintype "input"))
      (node (ref "X4") (pin "2") (pinfunction "S_2") (pintype "passive"))
    )
    (net (code "87") (name "Net-(U$1-SDA)") (class "Default")
      (node (ref "U$1") (pin "15") (pinfunction "SDA_15") (pintype "bidirectional"))
      (node (ref "U$4") (pin "15") (pinfunction "SDA_15") (pintype "bidirectional"))
      (node (ref "X4") (pin "3") (pinfunction "S_3") (pintype "passive"))
    )
    (net (code "88") (name "Net-(U$4-A0)") (class "Default")
      (node (ref "RN1") (pin "2") (pinfunction "2_2") (pintype "passive"))
      (node (ref "SW2") (pin "6") (pinfunction "6_6") (pintype "passive"))
      (node (ref "U$4") (pin "1") (pinfunction "A0_1") (pintype "input"))
    )
    (net (code "89") (name "Net-(U$4-A1)") (class "Default")
      (node (ref "RN1") (pin "3") (pinfunction "3_3") (pintype "passive"))
      (node (ref "SW2") (pin "5") (pinfunction "5_5") (pintype "passive"))
      (node (ref "U$4") (pin "2") (pinfunction "A1_2") (pintype "input"))
    )
    (net (code "90") (name "Net-(U$4-A2)") (class "Default")
      (node (ref "RN1") (pin "4") (pinfunction "4_4") (pintype "passive"))
      (node (ref "SW2") (pin "4") (pinfunction "4_4") (pintype "passive"))
      (node (ref "U$4") (pin "3") (pinfunction "A2_3") (pintype "input"))
    )
    (net (code "91") (name "unconnected-(RN1-Pad5)") (class "Default")
      (node (ref "RN1") (pin "5") (pinfunction "5_5") (pintype "passive"))
    )
    (net (code "92") (name "unconnected-(RN2-Pad5)") (class "Default")
      (node (ref "RN2") (pin "5") (pinfunction "5_5") (pintype "passive"))
    )
    (net (code "93") (name "unconnected-(U$1-{slash}INT-Pad13)") (class "Default")
      (node (ref "U$1") (pin "13") (pinfunction "/INT_13") (pintype "output"))
    )
    (net (code "94") (name "unconnected-(U$4-{slash}INT-Pad13)") (class "Default")
      (node (ref "U$4") (pin "13") (pinfunction "/INT_13") (pintype "output"))
    )
    (net (code "95") (name "unconnected-(X4A-S-Pad1)") (class "Default")
      (node (ref "X4") (pin "1") (pinfunction "S_1") (pintype "passive"))
    )
    (net (code "96") (name "unconnected-(X4B-S-Pad10)") (class "Default")
      (node (ref "X4") (pin "10") (pinfunction "S_10") (pintype "passive"))
    )
    (net (code "97") (name "unconnected-(X4C-S-Pad11)") (class "Default")
      (node (ref "X4") (pin "11") (pinfunction "S_11") (pintype "passive"))
    )
    (net (code "98") (name "unconnected-(X4D-S-Pad12)") (class "Default")
      (node (ref "X4") (pin "12") (pinfunction "S_12") (pintype "passive"))
    )
    (net (code "99") (name "unconnected-(X4K-S-Pad4)") (class "Default")
      (node (ref "X4") (pin "4") (pinfunction "S_4") (pintype "passive"))
    )
    (net (code "100") (name "unconnected-(X4L-S-Pad5)") (class "Default")
      (node (ref "X4") (pin "5") (pinfunction "S_5") (pintype "passive"))
    )
    (net (code "101") (name "unconnected-(X4M-S-Pad6)") (class "Default")
      (node (ref "X4") (pin "6") (pinfunction "S_6") (pintype "passive"))
    )
    (net (code "102") (name "unconnected-(X4N-S-Pad7)") (class "Default")
      (node (ref "X4") (pin "7") (pinfunction "S_7") (pintype "passive"))
    )
    (net (code "103") (name "unconnected-(X4O-S-Pad8)") (class "Default")
      (node (ref "X4") (pin "8") (pinfunction "S_8") (pintype "passive"))
    )
    (net (code "104") (name "unconnected-(X4P-S-Pad9)") (class "Default")
      (node (ref "X4") (pin "9") (pinfunction "S_9") (pintype "passive"))
    )
  )
)
